# EncConn2.net
KiCad netlist of a schematic drawn in EAGLE
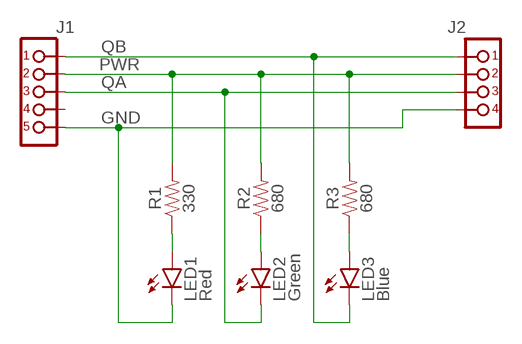
[diagram p0: schematic, sheet 1]

(export (version "E")
  (design (tool "Eeschema 10.0.6"))
  (components
    (comp (ref "J1")
      (value "HDR-5")
      (footprint "eagle-import:POST1X5")
      (libsource (lib "eagle-import") (part "HDR-5"))
    )
    (comp (ref "J2")
      (value "HDR-4NYLON-4")
      (footprint "eagle-import:NYLON-4")
      (libsource (lib "eagle-import") (part "HDR-4NYLON-4"))
    )
    (comp (ref "LED1")
      (value "Red")
      (footprint "eagle-import:SML0805")
      (libsource (lib "eagle-import") (part "LEDSML0805"))
    )
    (comp (ref "LED2")
      (value "Green")
      (footprint "eagle-import:SML0805")
      (libsource (lib "eagle-import") (part "LEDSML0805"))
    )
    (comp (ref "LED3")
      (value "Blue")
      (footprint "eagle-import:SML0805")
      (libsource (lib "eagle-import") (part "LEDSML0805"))
    )
    (comp (ref "R1")
      (value "330")
      (footprint "eagle-import:0805")
      (libsource (lib "eagle-import") (part "0.3OHM-0805-1/8W-1%"))
    )
    (comp (ref "R2")
      (value "680")
      (footprint "eagle-import:0805")
      (libsource (lib "eagle-import") (part "0.3OHM-0805-1/8W-1%"))
    )
    (comp (ref "R3")
      (value "680")
      (footprint "eagle-import:0805")
      (libsource (lib "eagle-import") (part "0.3OHM-0805-1/8W-1%"))
    )
  )
  (nets
    (net (code "1") (name "/GND") (class "Default")
      (node (ref "J1") (pin "5") (pinfunction "5_5") (pintype "passive"))
      (node (ref "J2") (pin "P$4") (pinfunction "4_P$4") (pintype "passive"))
      (node (ref "LED1") (pin "C") (pinfunction "C_C") (pintype "passive"))
    )
    (net (code "2") (name "/PWR") (class "Default")
      (node (ref "J1") (pin "2") (pinfunction "2_2") (pintype "passive"))
      (node (ref "J2") (pin "P$2") (pinfunction "2_P$2") (pintype "passive"))
      (node (ref "R1") (pin "2") (pinfunction "2_2") (pintype "passive"))
      (node (ref "R2") (pin "2") (pinfunction "2_2") (pintype "passive"))
      (node (ref "R3") (pin "2") (pinfunction "2_2") (pintype "passive"))
    )
    (net (code "3") (name "/QA") (class "Default")
      (node (ref "J1") (pin "3") (pinfunction "3_3") (pintype "passive"))
      (node (ref "J2") (pin "P$3") (pinfunction "3_P$3") (pintype "passive"))
      (node (ref "LED2") (pin "C") (pinfunction "C_C") (pintype "passive"))
    )
    (net (code "4") (name "/QB") (class "Default")
      (node (ref "J1") (pin "1") (pinfunction "1_1") (pintype "passive"))
      (node (ref "J2") (pin "P$1") (pinfunction "1_P$1") (pintype "passive"))
      (node (ref "LED3") (pin "C") (pinfunction "C_C") (pintype "passive"))
    )
    (net (code "5") (name "Net-(LED1-PadA)") (class "Default")
      (node (ref "LED1") (pin "A") (pinfunction "A_A") (pintype "passive"))
      (node (ref "R1") (pin "1") (pinfunction "1_1") (pintype "passive"))
    )
    (net (code "6") (name "Net-(LED2-PadA)") (class "Default")
      (node (ref "LED2") (pin "A") (pinfunction "A_A") (pintype "passive"))
      (node (ref "R2") (pin "1") (pinfunction "1_1") (pintype "passive"))
    )
    (net (code "7") (name "Net-(LED3-PadA)") (class "Default")
      (node (ref "LED3") (pin "A") (pinfunction "A_A") (pintype "passive"))
      (node (ref "R3") (pin "1") (pinfunction "1_1") (pintype "passive"))
    )
    (net (code "8") (name "unconnected-(J1-Pad4)") (class "Default")
      (node (ref "J1") (pin "4") (pinfunction "4_4") (pintype "passive"))
    )
  )
)
